# Input_Output.net
KiCad netlist of a schematic drawn in Altium Designer
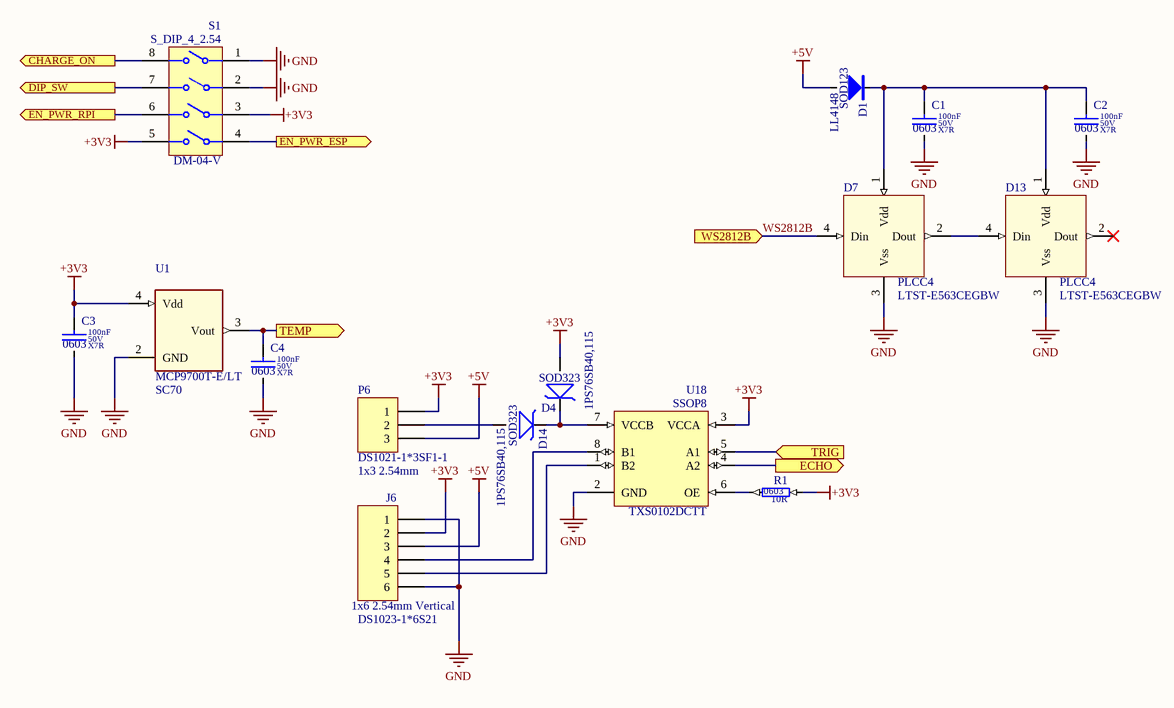
[diagram p0: Input_Output.SchDoc]

(export (version "E")
  (design (tool "Eeschema 10.0.6"))
  (components
    (comp (ref "C1")
      (value "100nF")
      (footprint "C_0603_1608")
      (description "Capacitor")
      (fields
        (field (name "DIELECTRIC") "X7R")
        (field (name "VOLTAGE") "50V")
        (field (name "SCH_FOOTPRINT") "0603")
        (field (name "PART NUMBER") "C_100nF_50V_X7R_0603_5")
        (field (name "MANUFACTURER") "Samsung")
      )
      (libsource (lib "Library") (part "C"))
    )
    (comp (ref "C2")
      (value "100nF")
      (footprint "C_0603_1608")
      (description "Capacitor")
      (fields
        (field (name "DIELECTRIC") "X7R")
        (field (name "VOLTAGE") "50V")
        (field (name "SCH_FOOTPRINT") "0603")
        (field (name "PART NUMBER") "C_100nF_50V_X7R_0603_5")
        (field (name "MANUFACTURER") "Samsung")
      )
      (libsource (lib "Library") (part "C"))
    )
    (comp (ref "C3")
      (value "100nF")
      (footprint "C_0603_1608")
      (description "Capacitor")
      (fields
        (field (name "DIELECTRIC") "X7R")
        (field (name "VOLTAGE") "50V")
        (field (name "SCH_FOOTPRINT") "0603")
        (field (name "PART NUMBER") "C_100nF_50V_X7R_0603_5")
        (field (name "MANUFACTURER") "Samsung")
      )
      (libsource (lib "Library") (part "C"))
    )
    (comp (ref "C4")
      (value "100nF")
      (footprint "C_0603_1608")
      (description "Capacitor")
      (fields
        (field (name "DIELECTRIC") "X7R")
        (field (name "VOLTAGE") "50V")
        (field (name "SCH_FOOTPRINT") "0603")
        (field (name "PART NUMBER") "C_100nF_50V_X7R_0603_5")
        (field (name "MANUFACTURER") "Samsung")
      )
      (libsource (lib "Library") (part "C"))
    )
    (comp (ref "D1")
      (value "LL4148")
      (footprint "SOD123")
      (fields
        (field (name "SCH_FOOTPRINT") "SOD123")
        (field (name "PART NUMBER") "D_1N4148W_0A15_75V_SOD123")
        (field (name "VOLTAGE") "75V")
        (field (name "MANUFACTURER") "Fairchild Semiconductor")
      )
      (libsource (lib "Library") (part "D"))
    )
    (comp (ref "D4")
      (value "1PS76SB40,115")
      (footprint "SOD323")
      (fields
        (field (name "SCH_FOOTPRINT") "SOD323")
        (field (name "PART NUMBER") "DS_1PS76SB40_40V_SOD323")
        (field (name "VOLTAGE") "40V")
        (field (name "MANUFACTURER") "Nexperia")
      )
      (libsource (lib "Library") (part "DS"))
    )
    (comp (ref "D7")
      (value "LTST-E563CEGBW")
      (footprint "PLCC4_5050")
      (fields
        (field (name "SCH_FOOTPRINT") "PLCC4")
        (field (name "PART NUMBER") "OL_LTST-E563CEGBW")
        (field (name "MANUFACTURER") "Lite-On")
        (field (name "Comment") "SMD LED with built-in embedded IC")
      )
      (libsource (lib "Library") (part "OL_WS2812B"))
    )
    (comp (ref "D13")
      (value "LTST-E563CEGBW")
      (footprint "PLCC4_5050")
      (fields
        (field (name "SCH_FOOTPRINT") "PLCC4")
        (field (name "PART NUMBER") "OL_LTST-E563CEGBW")
        (field (name "MANUFACTURER") "Lite-On")
        (field (name "Comment") "SMD LED with built-in embedded IC")
      )
      (libsource (lib "Library") (part "OL_WS2812B"))
    )
    (comp (ref "D14")
      (value "1PS76SB40,115")
      (footprint "SOD323")
      (fields
        (field (name "SCH_FOOTPRINT") "SOD323")
        (field (name "PART NUMBER") "DS_1PS76SB40_40V_SOD323")
        (field (name "VOLTAGE") "40V")
        (field (name "MANUFACTURER") "Nexperia")
      )
      (libsource (lib "Library") (part "DS"))
    )
    (comp (ref "J6")
      (value "DS1023-1*6S21")
      (footprint "J_HEADER_1x6_2.54_VERTICAL")
      (description "Header, 6-Pin")
      (fields
        (field (name "SCH_FOOTPRINT") "1x6 2.54mm Vertical")
        (field (name "PART NUMBER") "J_HEADER_1x6_2.54_VERTICAL")
        (field (name "MANUFACTURER") "Connfly")
      )
      (libsource (lib "Library") (part "J_HEADER_1x6"))
    )
    (comp (ref "P6")
      (value "DS1021-1*3SF1-1")
      (footprint "P_HEADER_1x3_2.54")
      (description "Header, 3-Pin")
      (fields
        (field (name "PART NUMBER") "P_HEADER_1x3_2.54")
        (field (name "SCH_FOOTPRINT") "1x3 2.54mm")
        (field (name "MANUFACTURER") "Connfly")
      )
      (libsource (lib "Library") (part "P_HEADER_1x3"))
    )
    (comp (ref "R1")
      (value "10R")
      (footprint "R_0603_1608")
      (fields
        (field (name "SCH_FOOTPRINT") "0603")
        (field (name "PART NUMBER") "R_10R_0603_1")
        (field (name "VOLTAGE") "50V")
        (field (name "POWER") "100mW")
      )
      (libsource (lib "Library") (part "R"))
    )
    (comp (ref "S1")
      (value "DM-04-V")
      (footprint "DM-04-V")
      (fields
        (field (name "SCH_FOOTPRINT") "S_DIP_4_2.54")
        (field (name "PART NUMBER") "S_DM-04-V")
        (field (name "MANUFACTURER") "DIPTRONICS")
        (field (name "Comment") "DIP SWITCH 4 POS")
      )
      (libsource (lib "Library") (part "S_DIP_SWITCH_4"))
    )
    (comp (ref "U1")
      (value "MCP9700T-E/LT")
      (footprint "SC70-5_SOT353_TSSOP5")
      (fields
        (field (name "PART NUMBER") "U_MCP9700T-E/LT")
        (field (name "SCH_FOOTPRINT") "SC70")
        (field (name "MANUFACTURER") "Microchip")
      )
      (libsource (lib "Library") (part "U_MCP9700T-E_LT"))
    )
    (comp (ref "U18")
      (value "TXS0102DCTT")
      (footprint "SSOP8_3x3")
      (fields
        (field (name "SCH_FOOTPRINT") "SSOP8")
        (field (name "PART NUMBER") "U_TXS0102DCTT")
        (field (name "MANUFACTURER") "Texas Instruments")
      )
      (libsource (lib "Library") (part "U_TXS0102_DCT_DCU"))
    )
  )
  (nets
    (net (code "1") (name "+3V3") (class "Default")
      (node (ref "C3") (pin "1") (pinfunction "1_1") (pintype "passive"))
      (node (ref "D4") (pin "2") (pintype "passive"))
      (node (ref "J6") (pin "2") (pinfunction "2_2") (pintype "passive"))
      (node (ref "P6") (pin "1") (pinfunction "1_1") (pintype "passive"))
      (node (ref "R1") (pin "1") (pinfunction "1_1") (pintype "input"))
      (node (ref "S1") (pin "3") (pinfunction "3_3") (pintype "passive"))
      (node (ref "S1") (pin "5") (pinfunction "5_5") (pintype "passive"))
      (node (ref "U1") (pin "4") (pinfunction "Vdd_4") (pintype "input"))
      (node (ref "U18") (pin "3") (pinfunction "VCCA_3") (pintype "input"))
    )
    (net (code "2") (name "+5V") (class "Default")
      (node (ref "D1") (pin "2") (pintype "passive"))
      (node (ref "J6") (pin "3") (pinfunction "3_3") (pintype "passive"))
      (node (ref "P6") (pin "3") (pinfunction "3_3") (pintype "passive"))
    )
    (net (code "3") (name "/CHARGE_ON") (class "Default")
      (node (ref "S1") (pin "8") (pinfunction "8_8") (pintype "passive"))
    )
    (net (code "4") (name "/DIP_SW") (class "Default")
      (node (ref "S1") (pin "7") (pinfunction "7_7") (pintype "passive"))
    )
    (net (code "5") (name "/ECHO") (class "Default")
      (node (ref "U18") (pin "4") (pinfunction "A2_4") (pintype "bidirectional"))
    )
    (net (code "6") (name "/EN_PWR_ESP") (class "Default")
      (node (ref "S1") (pin "4") (pinfunction "4_4") (pintype "passive"))
    )
    (net (code "7") (name "/EN_PWR_RPI") (class "Default")
      (node (ref "S1") (pin "6") (pinfunction "6_6") (pintype "passive"))
    )
    (net (code "8") (name "/TEMP") (class "Default")
      (node (ref "C4") (pin "1") (pinfunction "1_1") (pintype "passive"))
      (node (ref "U1") (pin "3") (pinfunction "Vout_3") (pintype "output"))
    )
    (net (code "9") (name "/TRIG") (class "Default")
      (node (ref "U18") (pin "5") (pinfunction "A1_5") (pintype "bidirectional"))
    )
    (net (code "10") (name "/WS2812B") (class "Default")
      (node (ref "D7") (pin "4") (pinfunction "Din_4") (pintype "input"))
    )
    (net (code "11") (name "GND") (class "Default")
      (node (ref "C1") (pin "2") (pinfunction "2_2") (pintype "passive"))
      (node (ref "C2") (pin "2") (pinfunction "2_2") (pintype "passive"))
      (node (ref "C3") (pin "2") (pinfunction "2_2") (pintype "passive"))
      (node (ref "C4") (pin "2") (pinfunction "2_2") (pintype "passive"))
      (node (ref "D13") (pin "3") (pinfunction "Vss_3") (pintype "power_in"))
      (node (ref "D7") (pin "3") (pinfunction "Vss_3") (pintype "power_in"))
      (node (ref "J6") (pin "1") (pinfunction "1_1") (pintype "passive"))
      (node (ref "J6") (pin "6") (pinfunction "6_6") (pintype "passive"))
      (node (ref "S1") (pin "1") (pinfunction "1_1") (pintype "passive"))
      (node (ref "S1") (pin "2") (pinfunction "2_2") (pintype "passive"))
      (node (ref "U1") (pin "2") (pinfunction "GND_2") (pintype "power_in"))
      (node (ref "U18") (pin "2") (pinfunction "GND_2") (pintype "power_in"))
    )
    (net (code "12") (name "Net-(D13-Din)") (class "Default")
      (node (ref "D13") (pin "4") (pinfunction "Din_4") (pintype "input"))
      (node (ref "D7") (pin "2") (pinfunction "Dout_2") (pintype "output"))
    )
    (net (code "13") (name "Net-(D13-Vdd)") (class "Default")
      (node (ref "C1") (pin "1") (pinfunction "1_1") (pintype "passive"))
      (node (ref "C2") (pin "1") (pinfunction "1_1") (pintype "passive"))
      (node (ref "D1") (pin "1") (pintype "passive"))
      (node (ref "D13") (pin "1") (pinfunction "Vdd_1") (pintype "input"))
      (node (ref "D7") (pin "1") (pinfunction "Vdd_1") (pintype "input"))
    )
    (net (code "14") (name "Net-(D14-Pad2)") (class "Default")
      (node (ref "D14") (pin "2") (pintype "passive"))
      (node (ref "P6") (pin "2") (pinfunction "2_2") (pintype "passive"))
    )
    (net (code "15") (name "Net-(U18-B1)") (class "Default")
      (node (ref "J6") (pin "4") (pinfunction "4_4") (pintype "passive"))
      (node (ref "U18") (pin "8") (pinfunction "B1_8") (pintype "bidirectional"))
    )
    (net (code "16") (name "Net-(U18-B2)") (class "Default")
      (node (ref "J6") (pin "5") (pinfunction "5_5") (pintype "passive"))
      (node (ref "U18") (pin "1") (pinfunction "B2_1") (pintype "bidirectional"))
    )
    (net (code "17") (name "Net-(U18-OE)") (class "Default")
      (node (ref "R1") (pin "2") (pinfunction "2_2") (pintype "output"))
      (node (ref "U18") (pin "6") (pinfunction "OE_6") (pintype "input"))
    )
    (net (code "18") (name "Net-(U18-VCCB)") (class "Default")
      (node (ref "D14") (pin "1") (pintype "passive"))
      (node (ref "D4") (pin "1") (pintype "passive"))
      (node (ref "U18") (pin "7") (pinfunction "VCCB_7") (pintype "input"))
    )
    (net (code "19") (name "unconnected-(D13-Dout-Pad2)") (class "Default")
      (node (ref "D13") (pin "2") (pinfunction "Dout_2") (pintype "output+no_connect"))
    )
  )
)
